# Design.net
KiCad netlist of a schematic drawn in EAGLE
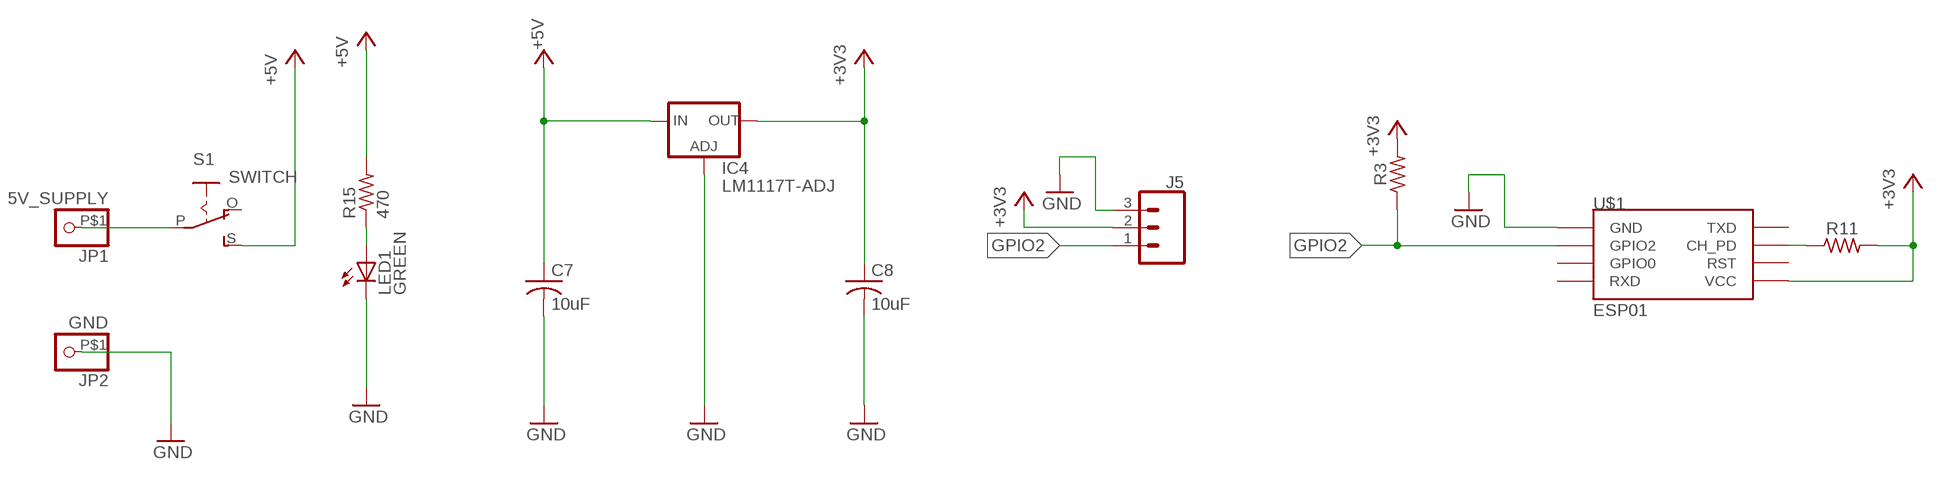
[diagram p0: schematic, sheet 1]

(export (version "E")
  (design (tool "Eeschema 10.0.6"))
  (components
    (comp (ref "C7")
      (value "10uF")
      (footprint "eagle-import:C025-025X050")
      (libsource (lib "eagle-import") (part "C-US025-025X050"))
    )
    (comp (ref "C8")
      (value "10uF")
      (footprint "eagle-import:C025-025X050")
      (libsource (lib "eagle-import") (part "C-US025-025X050"))
    )
    (comp (ref "IC4")
      (value "LM1117T-ADJ")
      (footprint "eagle-import:TO220")
      (libsource (lib "eagle-import") (part "LM1117T-ADJ"))
    )
    (comp (ref "J5")
      (value "1x3 RA Female .1\"")
      (footprint "eagle-import:1X03")
      (libsource (lib "eagle-import") (part "CONN_03"))
    )
    (comp (ref "JP1")
      (value "5V_SUPPLY")
      (footprint "eagle-import:1X1-BIGPOGO")
      (libsource (lib "eagle-import") (part "PINHD-1X1-BIGPOGO"))
    )
    (comp (ref "JP2")
      (value "GND")
      (footprint "eagle-import:1X1-BIGPOGO")
      (libsource (lib "eagle-import") (part "PINHD-1X1-BIGPOGO"))
    )
    (comp (ref "LED1")
      (value "GREEN")
      (footprint "eagle-import:LED5MM")
      (libsource (lib "eagle-import") (part "LED5MM"))
    )
    (comp (ref "R3")
      (value "10k")
      (footprint "eagle-import:0207_12")
      (libsource (lib "eagle-import") (part "R-US_0207/12"))
    )
    (comp (ref "R11")
      (value "10k")
      (footprint "eagle-import:0207_12")
      (libsource (lib "eagle-import") (part "R-US_0207/12"))
    )
    (comp (ref "R15")
      (value "470")
      (footprint "eagle-import:0207_12")
      (libsource (lib "eagle-import") (part "R-US_0207/12"))
    )
    (comp (ref "S1")
      (value "SWITCH")
      (footprint "eagle-import:EG1218")
      (libsource (lib "eagle-import") (part "EG1218S"))
    )
    (comp (ref "U$1")
      (value "ESP01")
      (footprint "eagle-import:ESP01")
      (libsource (lib "eagle-import") (part "ESP01"))
    )
  )
  (nets
    (net (code "1") (name "+3V3") (class "Default")
      (node (ref "C8") (pin "1") (pinfunction "1_1") (pintype "passive"))
      (node (ref "IC4") (pin "2") (pinfunction "OUT_2") (pintype "passive"))
      (node (ref "J5") (pin "2") (pinfunction "2_2") (pintype "passive"))
      (node (ref "R11") (pin "2") (pinfunction "2_2") (pintype "passive"))
      (node (ref "R3") (pin "2") (pinfunction "2_2") (pintype "passive"))
      (node (ref "U$1") (pin "VCC") (pinfunction "VCC_VCC") (pintype "bidirectional"))
    )
    (net (code "2") (name "+5V") (class "Default")
      (node (ref "C7") (pin "1") (pinfunction "1_1") (pintype "passive"))
      (node (ref "IC4") (pin "3") (pinfunction "IN_3") (pintype "input"))
      (node (ref "R15") (pin "2") (pinfunction "2_2") (pintype "passive"))
      (node (ref "S1") (pin "S") (pinfunction "S_S") (pintype "passive"))
    )
    (net (code "3") (name "GND") (class "Default")
      (node (ref "C7") (pin "2") (pinfunction "2_2") (pintype "passive"))
      (node (ref "C8") (pin "2") (pinfunction "2_2") (pintype "passive"))
      (node (ref "IC4") (pin "1") (pinfunction "ADJ_1") (pintype "input"))
      (node (ref "J5") (pin "3") (pinfunction "3_3") (pintype "passive"))
      (node (ref "JP2") (pin "P$1") (pinfunction "1_P$1") (pintype "passive"))
      (node (ref "LED1") (pin "K") (pinfunction "C_K") (pintype "passive"))
      (node (ref "U$1") (pin "GND") (pinfunction "GND_GND") (pintype "bidirectional"))
    )
    (net (code "4") (name "GPIO2") (class "Default")
      (node (ref "J5") (pin "1") (pinfunction "1_1") (pintype "passive"))
      (node (ref "R3") (pin "1") (pinfunction "1_1") (pintype "passive"))
      (node (ref "U$1") (pin "GPIO2") (pinfunction "GPIO2_GPIO2") (pintype "bidirectional"))
    )
    (net (code "5") (name "Net-(JP1-1)") (class "Default")
      (node (ref "JP1") (pin "P$1") (pinfunction "1_P$1") (pintype "passive"))
      (node (ref "S1") (pin "P") (pinfunction "P_P") (pintype "passive"))
    )
    (net (code "6") (name "Net-(LED1-PadA)") (class "Default")
      (node (ref "LED1") (pin "A") (pinfunction "A_A") (pintype "passive"))
      (node (ref "R15") (pin "1") (pinfunction "1_1") (pintype "passive"))
    )
    (net (code "7") (name "Net-(R11-Pad1)") (class "Default")
      (node (ref "R11") (pin "1") (pinfunction "1_1") (pintype "passive"))
      (node (ref "U$1") (pin "CH_PD") (pinfunction "CH_PD_CH_PD") (pintype "bidirectional"))
    )
    (net (code "8") (name "unconnected-(S1-PadO)") (class "Default")
      (node (ref "S1") (pin "O") (pinfunction "O_O") (pintype "passive"))
    )
    (net (code "9") (name "unconnected-(U$1-PadGPIO0)") (class "Default")
      (node (ref "U$1") (pin "GPIO0") (pinfunction "GPIO0_GPIO0") (pintype "bidirectional"))
    )
    (net (code "10") (name "unconnected-(U$1-PadRST)") (class "Default")
      (node (ref "U$1") (pin "RST") (pinfunction "RST_RST") (pintype "bidirectional"))
    )
    (net (code "11") (name "unconnected-(U$1-RXD-PadRX)") (class "Default")
      (node (ref "U$1") (pin "RX") (pinfunction "RXD_RX") (pintype "bidirectional"))
    )
    (net (code "12") (name "unconnected-(U$1-TXD-PadTX)") (class "Default")
      (node (ref "U$1") (pin "TX") (pinfunction "TXD_TX") (pintype "bidirectional"))
    )
  )
)
